# MEMS_MICs.net
KiCad netlist of a schematic drawn in Altium Designer
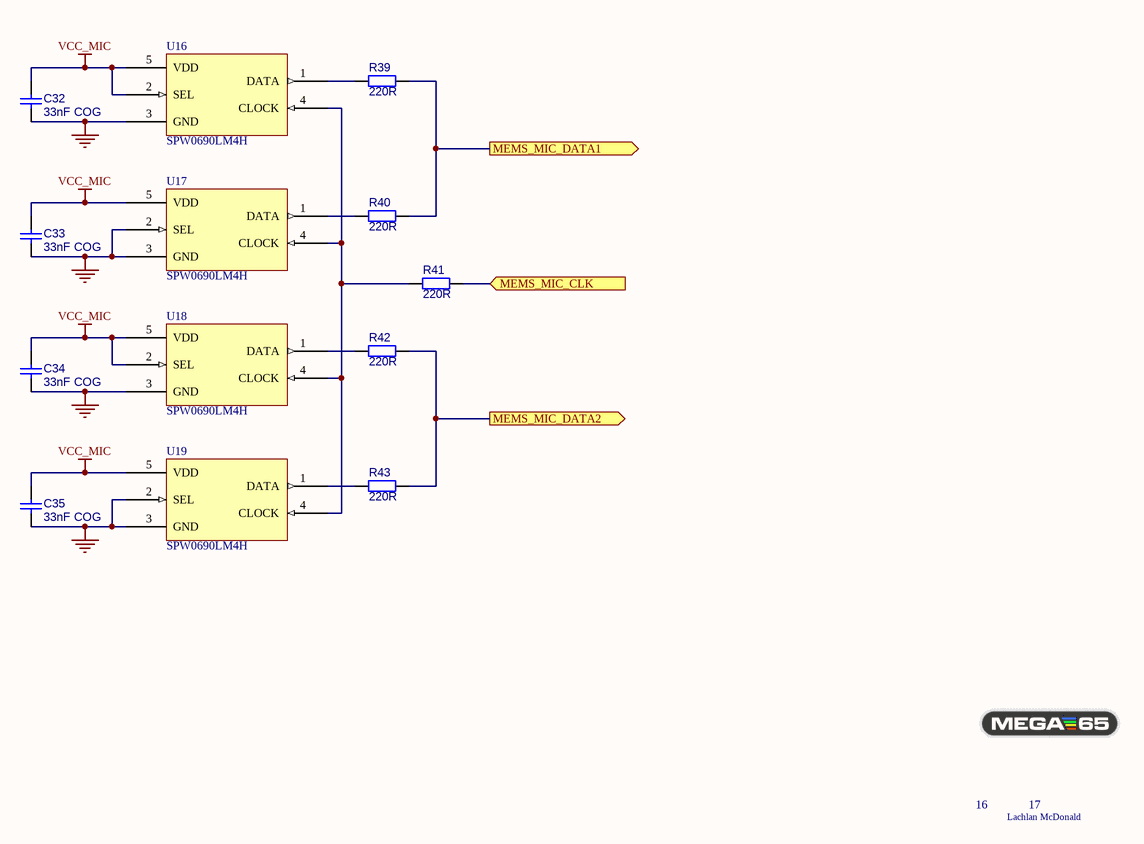
[diagram p0: MEMS MICs.SchDoc]

(export (version "E")
  (design (tool "Eeschema 10.0.6"))
  (components
    (comp (ref "C32")
      (value "33nF COG")
      (footprint "0805 Reflow Cap")
      (description "Capacitor")
      (fields (field (name "MANUFACTURER") "TDK Corporation"))
      (libsource (lib "Workshop Library 2010_06_24") (part "Cap"))
    )
    (comp (ref "C33")
      (value "33nF COG")
      (footprint "0805 Reflow Cap")
      (description "Capacitor")
      (fields (field (name "MANUFACTURER") "TDK Corporation"))
      (libsource (lib "Workshop Library 2010_06_24") (part "Cap"))
    )
    (comp (ref "C34")
      (value "33nF COG")
      (footprint "0805 Reflow Cap")
      (description "Capacitor")
      (fields (field (name "MANUFACTURER") "TDK Corporation"))
      (libsource (lib "Workshop Library 2010_06_24") (part "Cap"))
    )
    (comp (ref "C35")
      (value "33nF COG")
      (footprint "0805 Reflow Cap")
      (description "Capacitor")
      (fields (field (name "MANUFACTURER") "TDK Corporation"))
      (libsource (lib "Workshop Library 2010_06_24") (part "Cap"))
    )
    (comp (ref "R39")
      (value "220R")
      (footprint "0603-RESISTOR HD")
      (description "Resistor")
      (libsource (lib "Workshop Library 2010_06_24") (part "Resistor"))
    )
    (comp (ref "R40")
      (value "220R")
      (footprint "0603-RESISTOR HD")
      (description "Resistor")
      (libsource (lib "Workshop Library 2010_06_24") (part "Resistor"))
    )
    (comp (ref "R41")
      (value "220R")
      (footprint "0603-RESISTOR HD")
      (description "Resistor")
      (libsource (lib "Workshop Library 2010_06_24") (part "Resistor"))
    )
    (comp (ref "R42")
      (value "220R")
      (footprint "0603-RESISTOR HD")
      (description "Resistor")
      (libsource (lib "Workshop Library 2010_06_24") (part "Resistor"))
    )
    (comp (ref "R43")
      (value "220R")
      (footprint "0603-RESISTOR HD")
      (description "Resistor")
      (libsource (lib "Workshop Library 2010_06_24") (part "Resistor"))
    )
    (comp (ref "U16")
      (value "SPW0690LM4H")
      (footprint "MICROPHONE MEMS SPW0690LM4H-1")
      (fields (field (name "MANUFACTURER") "Knowles"))
      (libsource (lib "Schlib1") (part "MEMs Microphone"))
    )
    (comp (ref "U17")
      (value "SPW0690LM4H")
      (footprint "MICROPHONE MEMS SPW0690LM4H-1")
      (fields (field (name "MANUFACTURER") "Knowles"))
      (libsource (lib "Schlib1") (part "MEMs Microphone"))
    )
    (comp (ref "U18")
      (value "SPW0690LM4H")
      (footprint "MICROPHONE MEMS SPW0690LM4H-1")
      (fields (field (name "MANUFACTURER") "Knowles"))
      (libsource (lib "Schlib1") (part "MEMs Microphone"))
    )
    (comp (ref "U19")
      (value "SPW0690LM4H")
      (footprint "MICROPHONE MEMS SPW0690LM4H-1")
      (fields (field (name "MANUFACTURER") "Knowles"))
      (libsource (lib "Schlib1") (part "MEMs Microphone"))
    )
  )
  (nets
    (net (code "1") (name "/MEMS_MIC_CLK") (class "Default")
      (node (ref "R41") (pin "1") (pinfunction "1_1") (pintype "passive"))
    )
    (net (code "2") (name "/MEMS_MIC_DATA1") (class "Default")
      (node (ref "R39") (pin "1") (pinfunction "1_1") (pintype "passive"))
      (node (ref "R40") (pin "1") (pinfunction "1_1") (pintype "passive"))
    )
    (net (code "3") (name "/MEMS_MIC_DATA2") (class "Default")
      (node (ref "R42") (pin "1") (pinfunction "1_1") (pintype "passive"))
      (node (ref "R43") (pin "1") (pinfunction "1_1") (pintype "passive"))
    )
    (net (code "4") (name "GND") (class "Default")
      (node (ref "C32") (pin "2") (pinfunction "2_2") (pintype "passive"))
      (node (ref "C33") (pin "2") (pinfunction "2_2") (pintype "passive"))
      (node (ref "C34") (pin "2") (pinfunction "2_2") (pintype "passive"))
      (node (ref "C35") (pin "2") (pinfunction "2_2") (pintype "passive"))
      (node (ref "U16") (pin "3") (pinfunction "GND_3") (pintype "power_in"))
      (node (ref "U17") (pin "2") (pinfunction "SEL_2") (pintype "input"))
      (node (ref "U17") (pin "3") (pinfunction "GND_3") (pintype "power_in"))
      (node (ref "U18") (pin "3") (pinfunction "GND_3") (pintype "power_in"))
      (node (ref "U19") (pin "2") (pinfunction "SEL_2") (pintype "input"))
      (node (ref "U19") (pin "3") (pinfunction "GND_3") (pintype "power_in"))
    )
    (net (code "5") (name "Net-(U16-CLOCK)") (class "Default")
      (node (ref "R41") (pin "2") (pinfunction "2_2") (pintype "passive"))
      (node (ref "U16") (pin "4") (pinfunction "CLOCK_4") (pintype "input"))
      (node (ref "U17") (pin "4") (pinfunction "CLOCK_4") (pintype "input"))
      (node (ref "U18") (pin "4") (pinfunction "CLOCK_4") (pintype "input"))
      (node (ref "U19") (pin "4") (pinfunction "CLOCK_4") (pintype "input"))
    )
    (net (code "6") (name "Net-(U16-DATA)") (class "Default")
      (node (ref "R39") (pin "2") (pinfunction "2_2") (pintype "passive"))
      (node (ref "U16") (pin "1") (pinfunction "DATA_1") (pintype "output"))
    )
    (net (code "7") (name "Net-(U17-DATA)") (class "Default")
      (node (ref "R40") (pin "2") (pinfunction "2_2") (pintype "passive"))
      (node (ref "U17") (pin "1") (pinfunction "DATA_1") (pintype "output"))
    )
    (net (code "8") (name "Net-(U18-DATA)") (class "Default")
      (node (ref "R42") (pin "2") (pinfunction "2_2") (pintype "passive"))
      (node (ref "U18") (pin "1") (pinfunction "DATA_1") (pintype "output"))
    )
    (net (code "9") (name "Net-(U19-DATA)") (class "Default")
      (node (ref "R43") (pin "2") (pinfunction "2_2") (pintype "passive"))
      (node (ref "U19") (pin "1") (pinfunction "DATA_1") (pintype "output"))
    )
    (net (code "10") (name "VCC_MIC") (class "Default")
      (node (ref "C32") (pin "1") (pinfunction "1_1") (pintype "passive"))
      (node (ref "C33") (pin "1") (pinfunction "1_1") (pintype "passive"))
      (node (ref "C34") (pin "1") (pinfunction "1_1") (pintype "passive"))
      (node (ref "C35") (pin "1") (pinfunction "1_1") (pintype "passive"))
      (node (ref "U16") (pin "2") (pinfunction "SEL_2") (pintype "input"))
      (node (ref "U16") (pin "5") (pinfunction "VDD_5") (pintype "power_in"))
      (node (ref "U17") (pin "5") (pinfunction "VDD_5") (pintype "power_in"))
      (node (ref "U18") (pin "2") (pinfunction "SEL_2") (pintype "input"))
      (node (ref "U18") (pin "5") (pinfunction "VDD_5") (pintype "power_in"))
      (node (ref "U19") (pin "5") (pinfunction "VDD_5") (pintype "power_in"))
    )
  )
)
